# ghettoduino.net
KiCad netlist of a schematic drawn in EAGLE
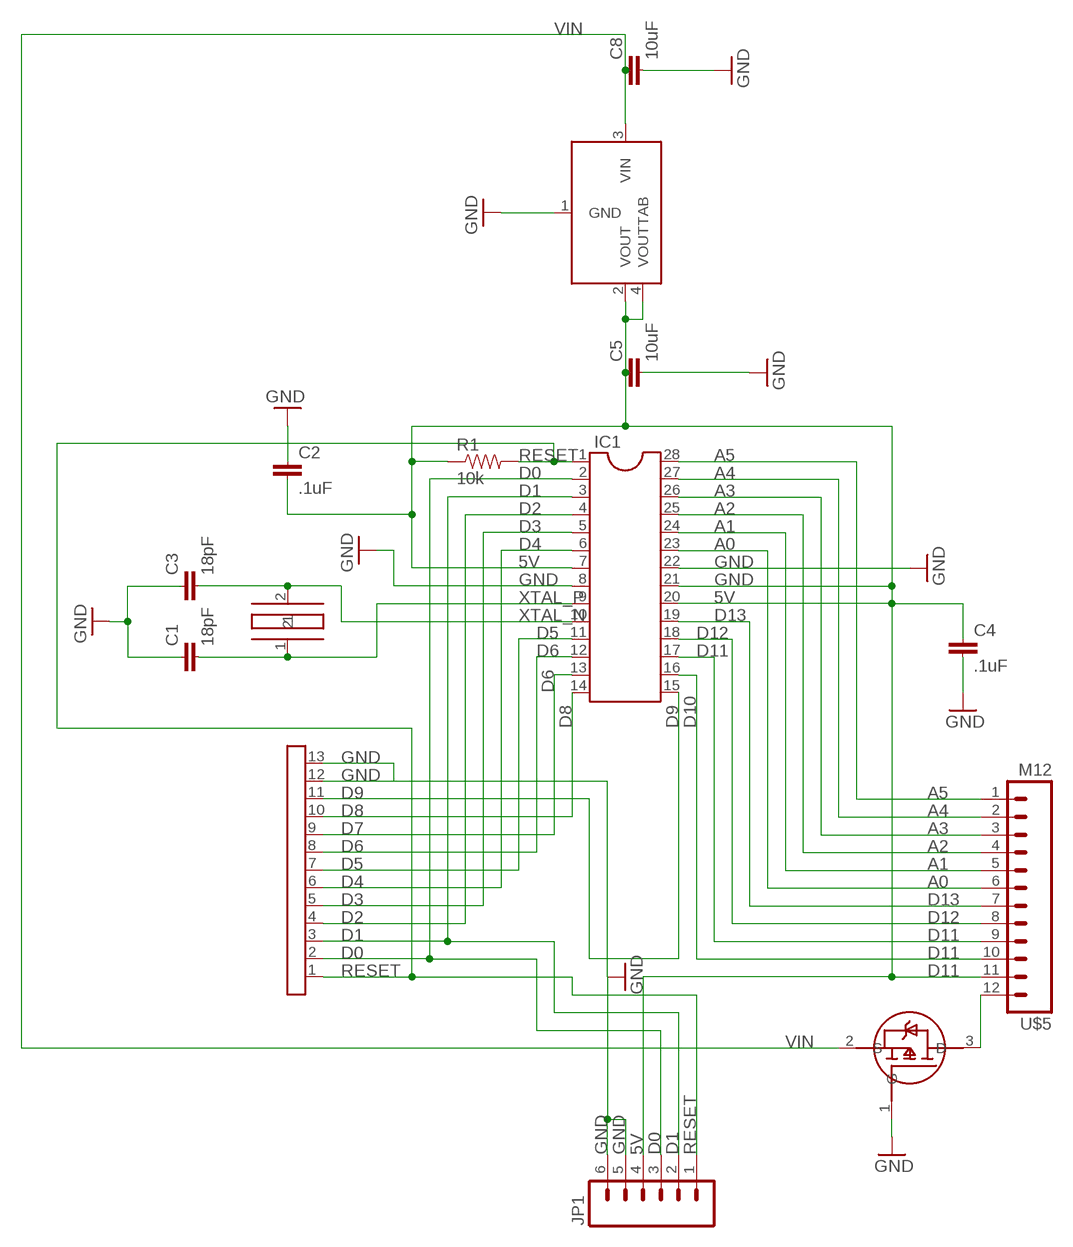
[diagram p0: schematic, sheet 1]

(export (version "E")
  (design (tool "Eeschema 10.0.6"))
  (components
    (comp (ref "5V")
      (value "5V-LDO-ZLDO1117")
      (footprint "eagle-import:ZLDO1117")
      (libsource (lib "eagle-import") (part "5V-LDO-ZLDO1117"))
    )
    (comp (ref "C1")
      (value "18pF")
      (footprint "eagle-import:0603-CAP")
      (libsource (lib "eagle-import") (part "CAP0603-CAP"))
    )
    (comp (ref "C2")
      (value ".1uF")
      (footprint "eagle-import:0805")
      (libsource (lib "eagle-import") (part "CAP0805"))
    )
    (comp (ref "C3")
      (value "18pF")
      (footprint "eagle-import:0603-CAP")
      (libsource (lib "eagle-import") (part "CAP0603-CAP"))
    )
    (comp (ref "C4")
      (value ".1uF")
      (footprint "eagle-import:0805")
      (libsource (lib "eagle-import") (part "CAP0805"))
    )
    (comp (ref "C5")
      (value "10uF")
      (footprint "eagle-import:1206")
      (libsource (lib "eagle-import") (part "CAP1206"))
    )
    (comp (ref "C8")
      (value "10uF")
      (footprint "eagle-import:1206")
      (libsource (lib "eagle-import") (part "CAP1206"))
    )
    (comp (ref "IC1")
      (value "DIL28-3")
      (footprint "eagle-import:DIL28-3")
      (libsource (lib "eagle-import") (part "DIL28-3"))
    )
    (comp (ref "JP1")
      (value "M06LOCK")
      (footprint "eagle-import:1X06_LOCK")
      (libsource (lib "eagle-import") (part "M06LOCK"))
    )
    (comp (ref "R1")
      (value "10k")
      (footprint "eagle-import:0805")
      (libsource (lib "eagle-import") (part "RESISTOR"))
    )
    (comp (ref "U$1")
      (value "HC49US")
      (footprint "eagle-import:HC49US")
      (libsource (lib "eagle-import") (part "HC49US"))
    )
    (comp (ref "U$2")
      (value "M12")
      (footprint "eagle-import:1X13_LOCK")
      (libsource (lib "eagle-import") (part "M13"))
    )
    (comp (ref "U$3")
      (value "P-MOSFET-PMV48XP")
      (footprint "eagle-import:SOT23-3LEAD")
      (libsource (lib "eagle-import") (part "P-MOSFET-PMV48XP"))
    )
    (comp (ref "U$5")
      (value "M12")
      (footprint "eagle-import:1X12_LOCK")
      (libsource (lib "eagle-import") (part "M12LOCK"))
    )
  )
  (nets
    (net (code "1") (name "/5V") (class "Default")
      (node (ref "5V") (pin "2") (pinfunction "VOUT_2") (pintype "bidirectional"))
      (node (ref "5V") (pin "4") (pinfunction "VOUTTAB_4") (pintype "bidirectional"))
      (node (ref "C2") (pin "2") (pinfunction "2_2") (pintype "passive"))
      (node (ref "C4") (pin "1") (pinfunction "1_1") (pintype "passive"))
      (node (ref "C5") (pin "1") (pinfunction "1_1") (pintype "passive"))
      (node (ref "IC1") (pin "20") (pinfunction "20_20") (pintype "passive"))
      (node (ref "IC1") (pin "21") (pinfunction "21_21") (pintype "passive"))
      (node (ref "IC1") (pin "7") (pinfunction "7_7") (pintype "passive"))
      (node (ref "JP1") (pin "4") (pinfunction "4_4") (pintype "passive"))
      (node (ref "R1") (pin "1") (pinfunction "1_1") (pintype "passive"))
      (node (ref "U$5") (pin "11") (pinfunction "11_11") (pintype "passive"))
    )
    (net (code "2") (name "/A0") (class "Default")
      (node (ref "IC1") (pin "23") (pinfunction "23_23") (pintype "passive"))
      (node (ref "U$5") (pin "6") (pinfunction "6_6") (pintype "passive"))
    )
    (net (code "3") (name "/A1") (class "Default")
      (node (ref "IC1") (pin "24") (pinfunction "24_24") (pintype "passive"))
      (node (ref "U$5") (pin "5") (pinfunction "5_5") (pintype "passive"))
    )
    (net (code "4") (name "/A2") (class "Default")
      (node (ref "IC1") (pin "25") (pinfunction "25_25") (pintype "passive"))
      (node (ref "U$5") (pin "4") (pinfunction "4_4") (pintype "passive"))
    )
    (net (code "5") (name "/A3") (class "Default")
      (node (ref "IC1") (pin "26") (pinfunction "26_26") (pintype "passive"))
      (node (ref "U$5") (pin "3") (pinfunction "3_3") (pintype "passive"))
    )
    (net (code "6") (name "/A4") (class "Default")
      (node (ref "IC1") (pin "27") (pinfunction "27_27") (pintype "passive"))
      (node (ref "U$5") (pin "2") (pinfunction "2_2") (pintype "passive"))
    )
    (net (code "7") (name "/A5") (class "Default")
      (node (ref "IC1") (pin "28") (pinfunction "28_28") (pintype "passive"))
      (node (ref "U$5") (pin "1") (pinfunction "1_1") (pintype "passive"))
    )
    (net (code "8") (name "/D0") (class "Default")
      (node (ref "IC1") (pin "2") (pinfunction "2_2") (pintype "passive"))
      (node (ref "JP1") (pin "3") (pinfunction "3_3") (pintype "passive"))
      (node (ref "U$2") (pin "2") (pinfunction "2_2") (pintype "bidirectional"))
    )
    (net (code "9") (name "/D1") (class "Default")
      (node (ref "IC1") (pin "3") (pinfunction "3_3") (pintype "passive"))
      (node (ref "JP1") (pin "2") (pinfunction "2_2") (pintype "passive"))
      (node (ref "U$2") (pin "3") (pinfunction "3_3") (pintype "bidirectional"))
    )
    (net (code "10") (name "/D2") (class "Default")
      (node (ref "IC1") (pin "4") (pinfunction "4_4") (pintype "passive"))
      (node (ref "U$2") (pin "4") (pinfunction "4_4") (pintype "bidirectional"))
    )
    (net (code "11") (name "/D3") (class "Default")
      (node (ref "IC1") (pin "5") (pinfunction "5_5") (pintype "passive"))
      (node (ref "U$2") (pin "5") (pinfunction "5_5") (pintype "bidirectional"))
    )
    (net (code "12") (name "/D4") (class "Default")
      (node (ref "IC1") (pin "6") (pinfunction "6_6") (pintype "passive"))
      (node (ref "U$2") (pin "6") (pinfunction "6_6") (pintype "bidirectional"))
    )
    (net (code "13") (name "/D5") (class "Default")
      (node (ref "IC1") (pin "11") (pinfunction "11_11") (pintype "passive"))
      (node (ref "U$2") (pin "7") (pinfunction "7_7") (pintype "bidirectional"))
    )
    (net (code "14") (name "/D6") (class "Default")
      (node (ref "IC1") (pin "12") (pinfunction "12_12") (pintype "passive"))
      (node (ref "U$2") (pin "8") (pinfunction "8_8") (pintype "bidirectional"))
    )
    (net (code "15") (name "/D7") (class "Default")
      (node (ref "IC1") (pin "13") (pinfunction "13_13") (pintype "passive"))
      (node (ref "U$2") (pin "9") (pinfunction "9_9") (pintype "bidirectional"))
    )
    (net (code "16") (name "/D8") (class "Default")
      (node (ref "IC1") (pin "14") (pinfunction "14_14") (pintype "passive"))
      (node (ref "U$2") (pin "10") (pinfunction "10_10") (pintype "bidirectional"))
    )
    (net (code "17") (name "/D9") (class "Default")
      (node (ref "IC1") (pin "15") (pinfunction "15_15") (pintype "passive"))
      (node (ref "U$2") (pin "11") (pinfunction "11_11") (pintype "bidirectional"))
    )
    (net (code "18") (name "/D10") (class "Default")
      (node (ref "IC1") (pin "16") (pinfunction "16_16") (pintype "passive"))
      (node (ref "U$5") (pin "10") (pinfunction "10_10") (pintype "passive"))
    )
    (net (code "19") (name "/D11") (class "Default")
      (node (ref "IC1") (pin "17") (pinfunction "17_17") (pintype "passive"))
      (node (ref "U$5") (pin "9") (pinfunction "9_9") (pintype "passive"))
    )
    (net (code "20") (name "/D12") (class "Default")
      (node (ref "IC1") (pin "18") (pinfunction "18_18") (pintype "passive"))
      (node (ref "U$5") (pin "8") (pinfunction "8_8") (pintype "passive"))
    )
    (net (code "21") (name "/D13") (class "Default")
      (node (ref "IC1") (pin "19") (pinfunction "19_19") (pintype "passive"))
      (node (ref "U$5") (pin "7") (pinfunction "7_7") (pintype "passive"))
    )
    (net (code "22") (name "/RESET") (class "Default")
      (node (ref "IC1") (pin "1") (pinfunction "1_1") (pintype "passive"))
      (node (ref "JP1") (pin "1") (pinfunction "1_1") (pintype "passive"))
      (node (ref "R1") (pin "2") (pinfunction "2_2") (pintype "passive"))
      (node (ref "U$2") (pin "1") (pinfunction "1_1") (pintype "bidirectional"))
    )
    (net (code "23") (name "/VIN") (class "Default")
      (node (ref "5V") (pin "3") (pinfunction "VIN_3") (pintype "bidirectional"))
      (node (ref "C8") (pin "1") (pinfunction "1_1") (pintype "passive"))
      (node (ref "U$3") (pin "2") (pinfunction "S_2") (pintype "bidirectional"))
    )
    (net (code "24") (name "/XTAL_N") (class "Default")
      (node (ref "C3") (pin "2") (pinfunction "2_2") (pintype "passive"))
      (node (ref "IC1") (pin "10") (pinfunction "10_10") (pintype "passive"))
      (node (ref "U$1") (pin "2") (pinfunction "2_2") (pintype "bidirectional"))
    )
    (net (code "25") (name "/XTAL_P") (class "Default")
      (node (ref "C1") (pin "2") (pinfunction "2_2") (pintype "passive"))
      (node (ref "IC1") (pin "9") (pinfunction "9_9") (pintype "passive"))
      (node (ref "U$1") (pin "1") (pinfunction "1_1") (pintype "bidirectional"))
    )
    (net (code "26") (name "GND") (class "Default")
      (node (ref "5V") (pin "1") (pinfunction "GND_1") (pintype "bidirectional"))
      (node (ref "C1") (pin "1") (pinfunction "1_1") (pintype "passive"))
      (node (ref "C2") (pin "1") (pinfunction "1_1") (pintype "passive"))
      (node (ref "C3") (pin "1") (pinfunction "1_1") (pintype "passive"))
      (node (ref "C4") (pin "2") (pinfunction "2_2") (pintype "passive"))
      (node (ref "C5") (pin "2") (pinfunction "2_2") (pintype "passive"))
      (node (ref "C8") (pin "2") (pinfunction "2_2") (pintype "passive"))
      (node (ref "IC1") (pin "22") (pinfunction "22_22") (pintype "passive"))
      (node (ref "IC1") (pin "8") (pinfunction "8_8") (pintype "passive"))
      (node (ref "JP1") (pin "5") (pinfunction "5_5") (pintype "passive"))
      (node (ref "JP1") (pin "6") (pinfunction "6_6") (pintype "passive"))
      (node (ref "U$2") (pin "12") (pinfunction "12_12") (pintype "bidirectional"))
      (node (ref "U$2") (pin "13") (pinfunction "13_13") (pintype "bidirectional"))
      (node (ref "U$3") (pin "1") (pinfunction "G_1") (pintype "bidirectional"))
    )
    (net (code "27") (name "Net-(U$3-D)") (class "Default")
      (node (ref "U$3") (pin "3") (pinfunction "D_3") (pintype "bidirectional"))
      (node (ref "U$5") (pin "12") (pinfunction "12_12") (pintype "passive"))
    )
  )
)
